# SD_Card.net
KiCad netlist of a schematic drawn in Altium Designer
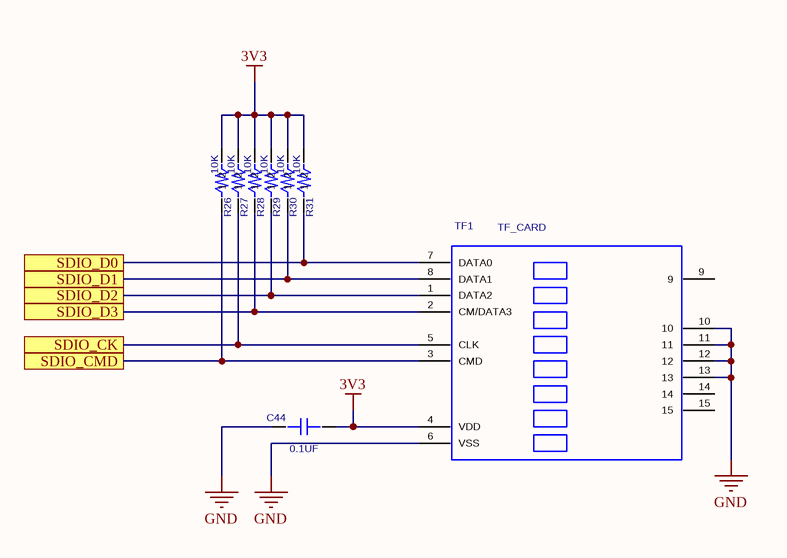
[diagram p0: SD_Card.SchDoc]

(export (version "E")
  (design (tool "Eeschema 10.0.6"))
  (components
    (comp (ref "C44")
      (value "0.1UF")
      (footprint "CAP_0603_FIRE")
      (description "SURFACE MOUNT CAPACITOR 0.031 X 0.061 INCHES")
      (fields (field (name "Comment") "CAP_0.1UF_0603_FIRE"))
      (libsource (lib "MINI-V3") (part "CAP_0.1UF_0603_FIRE"))
    )
    (comp (ref "R26")
      (value "10K")
      (footprint "RES_0603_FIRE")
      (description "SURFACE MOUNT RESISTOR 0.031 X 0.061 INCHES, 1/10W")
      (fields (field (name "Comment") "RES_10K_0603_FIRE"))
      (libsource (lib "MINI-V3") (part "RES_10K_0603_FIRE"))
    )
    (comp (ref "R27")
      (value "10K")
      (footprint "RES_0603_FIRE")
      (description "SURFACE MOUNT RESISTOR 0.031 X 0.061 INCHES, 1/10W")
      (fields (field (name "Comment") "RES_10K_0603_FIRE"))
      (libsource (lib "MINI-V3") (part "RES_10K_0603_FIRE"))
    )
    (comp (ref "R28")
      (value "10K")
      (footprint "RES_0603_FIRE")
      (description "SURFACE MOUNT RESISTOR 0.031 X 0.061 INCHES, 1/10W")
      (fields (field (name "Comment") "RES_10K_0603_FIRE"))
      (libsource (lib "MINI-V3") (part "RES_10K_0603_FIRE"))
    )
    (comp (ref "R29")
      (value "10K")
      (footprint "RES_0603_FIRE")
      (description "SURFACE MOUNT RESISTOR 0.031 X 0.061 INCHES, 1/10W")
      (fields (field (name "Comment") "RES_10K_0603_FIRE"))
      (libsource (lib "MINI-V3") (part "RES_10K_0603_FIRE"))
    )
    (comp (ref "R30")
      (value "10K")
      (footprint "RES_0603_FIRE")
      (description "SURFACE MOUNT RESISTOR 0.031 X 0.061 INCHES, 1/10W")
      (fields (field (name "Comment") "RES_10K_0603_FIRE"))
      (libsource (lib "MINI-V3") (part "RES_10K_0603_FIRE"))
    )
    (comp (ref "R31")
      (value "10K")
      (footprint "RES_0603_FIRE")
      (description "SURFACE MOUNT RESISTOR 0.031 X 0.061 INCHES, 1/10W")
      (fields (field (name "Comment") "RES_10K_0603_FIRE"))
      (libsource (lib "MINI-V3") (part "RES_10K_0603_FIRE"))
    )
    (comp (ref "TF1") (value "TF_CARD") (footprint "TF_CARD") (libsource (lib "MINI-V3") (part "TF_CARD")))
  )
  (nets
    (net (code "1") (name "/SDIO_CK") (class "Default")
      (node (ref "R27") (pin "1") (pinfunction "1_1") (pintype "passive"))
      (node (ref "TF1") (pin "5") (pinfunction "CLK_5") (pintype "passive"))
    )
    (net (code "2") (name "/SDIO_CMD") (class "Default")
      (node (ref "R26") (pin "1") (pinfunction "1_1") (pintype "passive"))
      (node (ref "TF1") (pin "3") (pinfunction "CMD_3") (pintype "passive"))
    )
    (net (code "3") (name "/SDIO_D0") (class "Default")
      (node (ref "R31") (pin "1") (pinfunction "1_1") (pintype "passive"))
      (node (ref "TF1") (pin "7") (pinfunction "DATA0_7") (pintype "passive"))
    )
    (net (code "4") (name "/SDIO_D1") (class "Default")
      (node (ref "R30") (pin "1") (pinfunction "1_1") (pintype "passive"))
      (node (ref "TF1") (pin "8") (pinfunction "DATA1_8") (pintype "passive"))
    )
    (net (code "5") (name "/SDIO_D2") (class "Default")
      (node (ref "R29") (pin "1") (pinfunction "1_1") (pintype "passive"))
      (node (ref "TF1") (pin "1") (pinfunction "DATA2_1") (pintype "passive"))
    )
    (net (code "6") (name "/SDIO_D3") (class "Default")
      (node (ref "R28") (pin "1") (pinfunction "1_1") (pintype "passive"))
      (node (ref "TF1") (pin "2") (pinfunction "CM/DATA3_2") (pintype "passive"))
    )
    (net (code "7") (name "3V3") (class "Default")
      (node (ref "C44") (pin "1") (pinfunction "1_1") (pintype "passive"))
      (node (ref "R26") (pin "2") (pinfunction "2_2") (pintype "passive"))
      (node (ref "R27") (pin "2") (pinfunction "2_2") (pintype "passive"))
      (node (ref "R28") (pin "2") (pinfunction "2_2") (pintype "passive"))
      (node (ref "R29") (pin "2") (pinfunction "2_2") (pintype "passive"))
      (node (ref "R30") (pin "2") (pinfunction "2_2") (pintype "passive"))
      (node (ref "R31") (pin "2") (pinfunction "2_2") (pintype "passive"))
      (node (ref "TF1") (pin "4") (pinfunction "VDD_4") (pintype "passive"))
    )
    (net (code "8") (name "GND") (class "Default")
      (node (ref "C44") (pin "2") (pinfunction "2_2") (pintype "passive"))
      (node (ref "TF1") (pin "10") (pinfunction "10_10") (pintype "passive"))
      (node (ref "TF1") (pin "11") (pinfunction "11_11") (pintype "passive"))
      (node (ref "TF1") (pin "12") (pinfunction "12_12") (pintype "passive"))
      (node (ref "TF1") (pin "13") (pinfunction "13_13") (pintype "passive"))
      (node (ref "TF1") (pin "6") (pinfunction "VSS_6") (pintype "passive"))
    )
    (net (code "9") (name "unconnected-(TF1-Pad9)") (class "Default")
      (node (ref "TF1") (pin "9") (pinfunction "9_9") (pintype "passive"))
    )
    (net (code "10") (name "unconnected-(TF1-Pad14)") (class "Default")
      (node (ref "TF1") (pin "14") (pinfunction "14_14") (pintype "passive"))
    )
    (net (code "11") (name "unconnected-(TF1-Pad15)") (class "Default")
      (node (ref "TF1") (pin "15") (pinfunction "15_15") (pintype "passive"))
    )
  )
)
